# 06_Power_Supply.net
KiCad netlist of a schematic drawn in Altium Designer
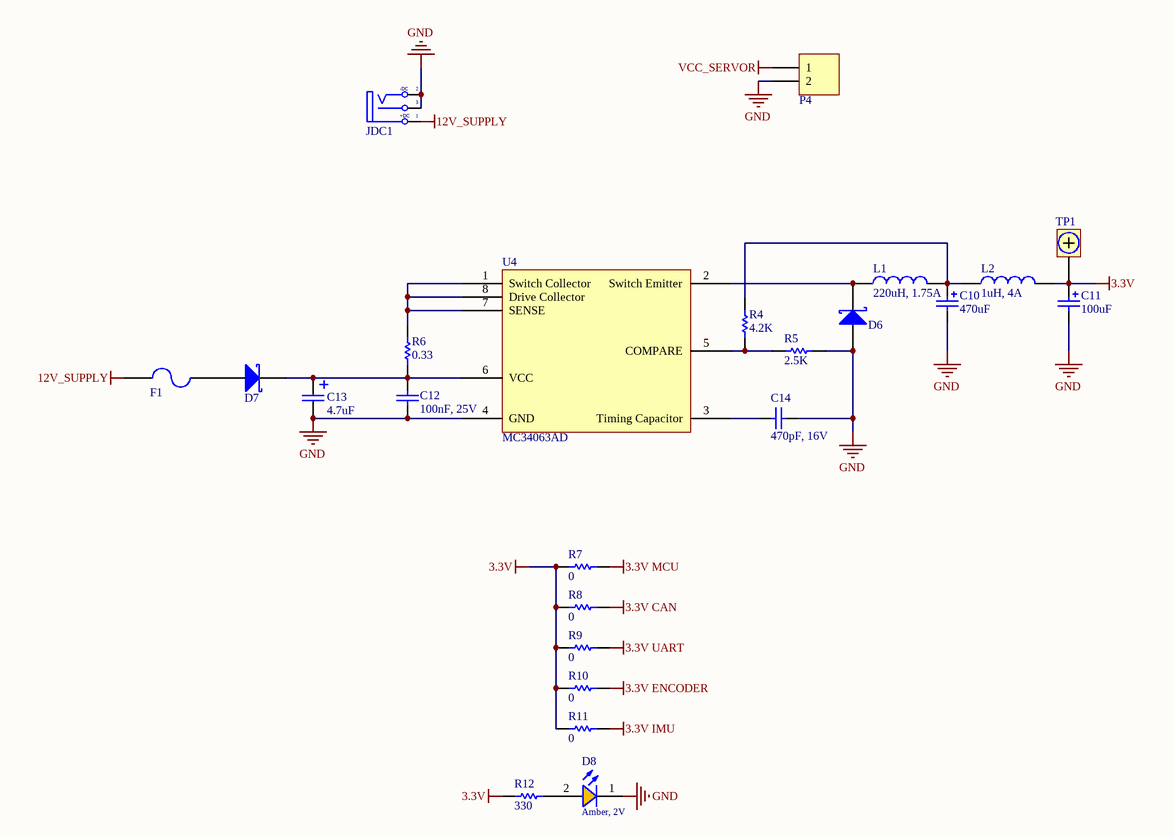
[diagram p0: 06_Power_Supply.SchDoc]

(export (version "E")
  (design (tool "Eeschema 10.0.6"))
  (components
    (comp (ref "C10")
      (value "470uF")
      (footprint "CAP ALU SIZE F")
      (description "Polarized Capacitor (Radial)")
      (fields (field (name "Comment") "Cap Pol SMD"))
      (libsource (lib "PIF_Library") (part "Cap Pol SMD"))
    )
    (comp (ref "C11")
      (value "100uF")
      (footprint "CAP ALU SIZE D")
      (description "Polarized Capacitor (Radial)")
      (fields (field (name "Comment") "Cap Pol SMD"))
      (libsource (lib "PIF_Library") (part "Cap Pol SMD"))
    )
    (comp (ref "C12")
      (value "100nF, 25V")
      (footprint "WCAP-CSGP_0603_H=0.8mm_Reflow")
      (description "WCAP-CSGP Multilayer Ceramic Chip Capacitor, General Purpose, size 0603, X7R, 100nF, 25V")
      (fields
        (field (name "MANUFACTURER PART NUMBER") "885012206071")
        (field (name "MANUFACTURER") "Wurth Elektronik")
      )
      (libsource (lib "Altium_WCAP-CSGP (rev20a)") (part "885012206071"))
    )
    (comp (ref "C13")
      (value "4.7uF")
      (footprint "CAPMP3216X18N")
      (fields (field (name "Comment") "Tantalum Capacitor"))
      (libsource (lib "MiclsLib") (part "Tantalum Capacitor"))
    )
    (comp (ref "C14")
      (value "470pF, 16V")
      (footprint "WCAP-CSGP_0603_H=0.8mm_Reflow")
      (description "WCAP-CSGP Multilayer Ceramic Chip Capacitor, General Purpose, size 0603, NP0, 470pF, 16V")
      (fields
        (field (name "MANUFACTURER PART NUMBER") "885012006027")
        (field (name "MANUFACTURER") "Wurth Elektronik")
      )
      (libsource (lib "Altium_WCAP-CSGP (rev20a)") (part "885012006027"))
    )
    (comp (ref "D6")
      (value "D Schottky")
      (footprint "SS34")
      (description "Schottky Diode")
      (fields (field (name "PUBLISHER") "Altium Limited"))
      (libsource (lib "PIF_Library") (part "D Schottky"))
    )
    (comp (ref "D7")
      (value "D Schottky")
      (footprint "SS34")
      (description "Schottky Diode")
      (fields (field (name "PUBLISHER") "Altium Limited"))
      (libsource (lib "PIF_Library") (part "D Schottky"))
    )
    (comp (ref "D8")
      (value "Amber, 2V")
      (footprint "WL-SMCW_0603_H=0.7mm")
      (description "WL-SMCW SMT Mono-color Chip LED Waterclear, size 0603, Amber, 2V, 140deg")
      (fields (field (name "PART NUMBER") "150060AS75000") (field (name "PUBLISHER") "Wurth Elektronik"))
      (libsource (lib "Altium_WL-SMCW (rev20a)") (part "150060AS75000"))
    )
    (comp (ref "F1") (value "Fuse") (footprint "FUSE SMD") (libsource (lib "PIF_Library") (part "Fuse")))
    (comp (ref "JDC1")
      (value "Jack DC")
      (footprint "DC-IN")
      (description "Jack DC input")
      (libsource (lib "PIF_Library") (part "Jack DC"))
    )
    (comp (ref "L1")
      (value "220uH, 1.75A")
      (footprint "WE-PD2A_5848")
      (description "WE-PD2A SMT Power Inductor, size 5848, 220uH, 0.41A")
      (fields
        (field (name "MANUFACTURER PART NUMBER") "784774222")
        (field (name "MANUFACTURER") "Wurth Elektronik")
      )
      (libsource (lib "Altium_WE-PD2A (rev20a)") (part "784774222"))
    )
    (comp (ref "L2")
      (value "1uH, 4A")
      (footprint "WE-PD2A_4532")
      (description "WE-PD2A SMT Power Inductor, size 4532, 1uH, 4A")
      (fields
        (field (name "MANUFACTURER PART NUMBER") "7847730")
        (field (name "MANUFACTURER") "Wurth Elektronik")
      )
      (libsource (lib "Altium_WE-PD2A (rev20a)") (part "7847730"))
    )
    (comp (ref "P4")
      (value "Domino 2")
      (footprint "DOMINO 2- 5mm")
      (description "Domino, 2-Pin")
      (fields (field (name "PUBLISHER") "Altium Limited"))
      (libsource (lib "PIF_Library") (part "Domino 2"))
    )
    (comp (ref "R4")
      (value "4.2K")
      (footprint "RES-SM-0603")
      (description "Resistor")
      (fields (field (name "Comment") "RESISTOR SMD"))
      (libsource (lib "PIF_Library") (part "RESISTOR SMD"))
    )
    (comp (ref "R5")
      (value "2.5K")
      (footprint "RES-SM-0603")
      (description "Resistor")
      (fields (field (name "Comment") "RESISTOR SMD"))
      (libsource (lib "PIF_Library") (part "RESISTOR SMD"))
    )
    (comp (ref "R6")
      (value "0.33")
      (footprint "RES-SM-0805")
      (description "Resistor")
      (fields (field (name "Comment") "RESISTOR SMD"))
      (libsource (lib "PIF_Library") (part "RESISTOR SMD"))
    )
    (comp (ref "R7")
      (value "0")
      (footprint "RES-SM-0805")
      (description "Resistor")
      (fields (field (name "Comment") "RESISTOR SMD"))
      (libsource (lib "PIF_Library") (part "RESISTOR SMD"))
    )
    (comp (ref "R8")
      (value "0")
      (footprint "RES-SM-0805")
      (description "Resistor")
      (fields (field (name "Comment") "RESISTOR SMD"))
      (libsource (lib "PIF_Library") (part "RESISTOR SMD"))
    )
    (comp (ref "R9")
      (value "0")
      (footprint "RES-SM-0805")
      (description "Resistor")
      (fields (field (name "Comment") "RESISTOR SMD"))
      (libsource (lib "PIF_Library") (part "RESISTOR SMD"))
    )
    (comp (ref "R10")
      (value "0")
      (footprint "RES-SM-0805")
      (description "Resistor")
      (fields (field (name "Comment") "RESISTOR SMD"))
      (libsource (lib "PIF_Library") (part "RESISTOR SMD"))
    )
    (comp (ref "R11")
      (value "0")
      (footprint "RES-SM-0805")
      (description "Resistor")
      (fields (field (name "Comment") "RESISTOR SMD"))
      (libsource (lib "PIF_Library") (part "RESISTOR SMD"))
    )
    (comp (ref "R12")
      (value "330")
      (footprint "RES-SM-0603")
      (description "Resistor")
      (fields (field (name "Comment") "RESISTOR SMD"))
      (libsource (lib "PIF_Library") (part "RESISTOR SMD"))
    )
    (comp (ref "TP1") (value "Test point") (footprint "TP") (libsource (lib "MiclsLib") (part "TP")))
    (comp (ref "U4")
      (value "MC34063AD")
      (footprint "SOIC127P600X170-8N")
      (description "1.5-A boost, buck, inverting switching regulator, operation from 0°C to 70°C")
      (fields (field (name "MANUFACTURER") "Texas Instruments"))
      (libsource (lib "PowerSupply") (part "MC34063"))
    )
  )
  (nets
    (net (code "1") (name "3.3V") (class "Default")
      (node (ref "C11") (pin "1") (pinfunction "1_1") (pintype "passive"))
      (node (ref "L2") (pin "2") (pinfunction "2_2") (pintype "passive"))
      (node (ref "R10") (pin "2") (pinfunction "2_2") (pintype "passive"))
      (node (ref "R11") (pin "2") (pinfunction "2_2") (pintype "passive"))
      (node (ref "R12") (pin "2") (pinfunction "2_2") (pintype "passive"))
      (node (ref "R7") (pin "2") (pinfunction "2_2") (pintype "passive"))
      (node (ref "R8") (pin "2") (pinfunction "2_2") (pintype "passive"))
      (node (ref "R9") (pin "2") (pinfunction "2_2") (pintype "passive"))
      (node (ref "TP1") (pin "1") (pinfunction "27_1") (pintype "passive"))
    )
    (net (code "2") (name "3.3V CAN") (class "Default")
      (node (ref "R8") (pin "1") (pinfunction "1_1") (pintype "passive"))
    )
    (net (code "3") (name "3.3V ENCODER") (class "Default")
      (node (ref "R10") (pin "1") (pinfunction "1_1") (pintype "passive"))
    )
    (net (code "4") (name "3.3V IMU") (class "Default")
      (node (ref "R11") (pin "1") (pinfunction "1_1") (pintype "passive"))
    )
    (net (code "5") (name "3.3V MCU") (class "Default")
      (node (ref "R7") (pin "1") (pinfunction "1_1") (pintype "passive"))
    )
    (net (code "6") (name "3.3V UART") (class "Default")
      (node (ref "R9") (pin "1") (pinfunction "1_1") (pintype "passive"))
    )
    (net (code "7") (name "12V_SUPPLY") (class "Default")
      (node (ref "F1") (pin "1") (pinfunction "1_1") (pintype "passive"))
      (node (ref "JDC1") (pin "1") (pinfunction "T_1") (pintype "passive"))
    )
    (net (code "8") (name "GND") (class "Default")
      (node (ref "C10") (pin "2") (pinfunction "2_2") (pintype "passive"))
      (node (ref "C11") (pin "2") (pinfunction "2_2") (pintype "passive"))
      (node (ref "C12") (pin "1") (pinfunction "1_1") (pintype "passive"))
      (node (ref "C13") (pin "2") (pinfunction "2_2") (pintype "passive"))
      (node (ref "C14") (pin "2") (pinfunction "2_2") (pintype "passive"))
      (node (ref "D6") (pin "1") (pinfunction "A_1") (pintype "passive"))
      (node (ref "D8") (pin "1") (pinfunction "K_1") (pintype "passive"))
      (node (ref "JDC1") (pin "2") (pinfunction "TN_2") (pintype "passive"))
      (node (ref "JDC1") (pin "3") (pinfunction "S_3") (pintype "power_in"))
      (node (ref "P4") (pin "2") (pinfunction "2_2") (pintype "passive"))
      (node (ref "R5") (pin "1") (pinfunction "1_1") (pintype "passive"))
      (node (ref "U4") (pin "4") (pinfunction "GND_4") (pintype "passive"))
    )
    (net (code "9") (name "Net-(C10-Pad1)") (class "Default")
      (node (ref "C10") (pin "1") (pinfunction "1_1") (pintype "passive"))
      (node (ref "L1") (pin "2") (pinfunction "2_2") (pintype "passive"))
      (node (ref "L2") (pin "1") (pinfunction "1_1") (pintype "passive"))
      (node (ref "R4") (pin "2") (pinfunction "2_2") (pintype "passive"))
    )
    (net (code "10") (name "Net-(D6-K)") (class "Default")
      (node (ref "D6") (pin "2") (pinfunction "K_2") (pintype "passive"))
      (node (ref "L1") (pin "1") (pinfunction "1_1") (pintype "passive"))
      (node (ref "U4") (pin "2") (pinfunction "Switch_Emitter_2") (pintype "passive"))
    )
    (net (code "11") (name "Net-(D7-A)") (class "Default")
      (node (ref "D7") (pin "1") (pinfunction "A_1") (pintype "passive"))
      (node (ref "F1") (pin "2") (pinfunction "2_2") (pintype "passive"))
    )
    (net (code "12") (name "Net-(D7-K)") (class "Default")
      (node (ref "C12") (pin "2") (pinfunction "2_2") (pintype "passive"))
      (node (ref "C13") (pin "1") (pinfunction "1_1") (pintype "passive"))
      (node (ref "D7") (pin "2") (pinfunction "K_2") (pintype "passive"))
      (node (ref "R6") (pin "1") (pinfunction "1_1") (pintype "passive"))
      (node (ref "U4") (pin "6") (pinfunction "VCC_6") (pintype "passive"))
    )
    (net (code "13") (name "Net-(D8-A)") (class "Default")
      (node (ref "D8") (pin "2") (pinfunction "A_2") (pintype "passive"))
      (node (ref "R12") (pin "1") (pinfunction "1_1") (pintype "passive"))
    )
    (net (code "14") (name "Net-(U4-COMPARE)") (class "Default")
      (node (ref "R4") (pin "1") (pinfunction "1_1") (pintype "passive"))
      (node (ref "R5") (pin "2") (pinfunction "2_2") (pintype "passive"))
      (node (ref "U4") (pin "5") (pinfunction "COMPARE_5") (pintype "passive"))
    )
    (net (code "15") (name "Net-(U4-Drive_Collector)") (class "Default")
      (node (ref "R6") (pin "2") (pinfunction "2_2") (pintype "passive"))
      (node (ref "U4") (pin "1") (pinfunction "Switch_Collector_1") (pintype "passive"))
      (node (ref "U4") (pin "7") (pinfunction "SENSE_7") (pintype "passive"))
      (node (ref "U4") (pin "8") (pinfunction "Drive_Collector_8") (pintype "passive"))
    )
    (net (code "16") (name "Net-(U4-Timing_Capacitor)") (class "Default")
      (node (ref "C14") (pin "1") (pinfunction "1_1") (pintype "passive"))
      (node (ref "U4") (pin "3") (pinfunction "Timing_Capacitor_3") (pintype "passive"))
    )
    (net (code "17") (name "VCC_SERVOR") (class "Default")
      (node (ref "P4") (pin "1") (pinfunction "1_1") (pintype "passive"))
    )
  )
)
